# frontconnectors.net
KiCad netlist of a schematic drawn in Altium Designer
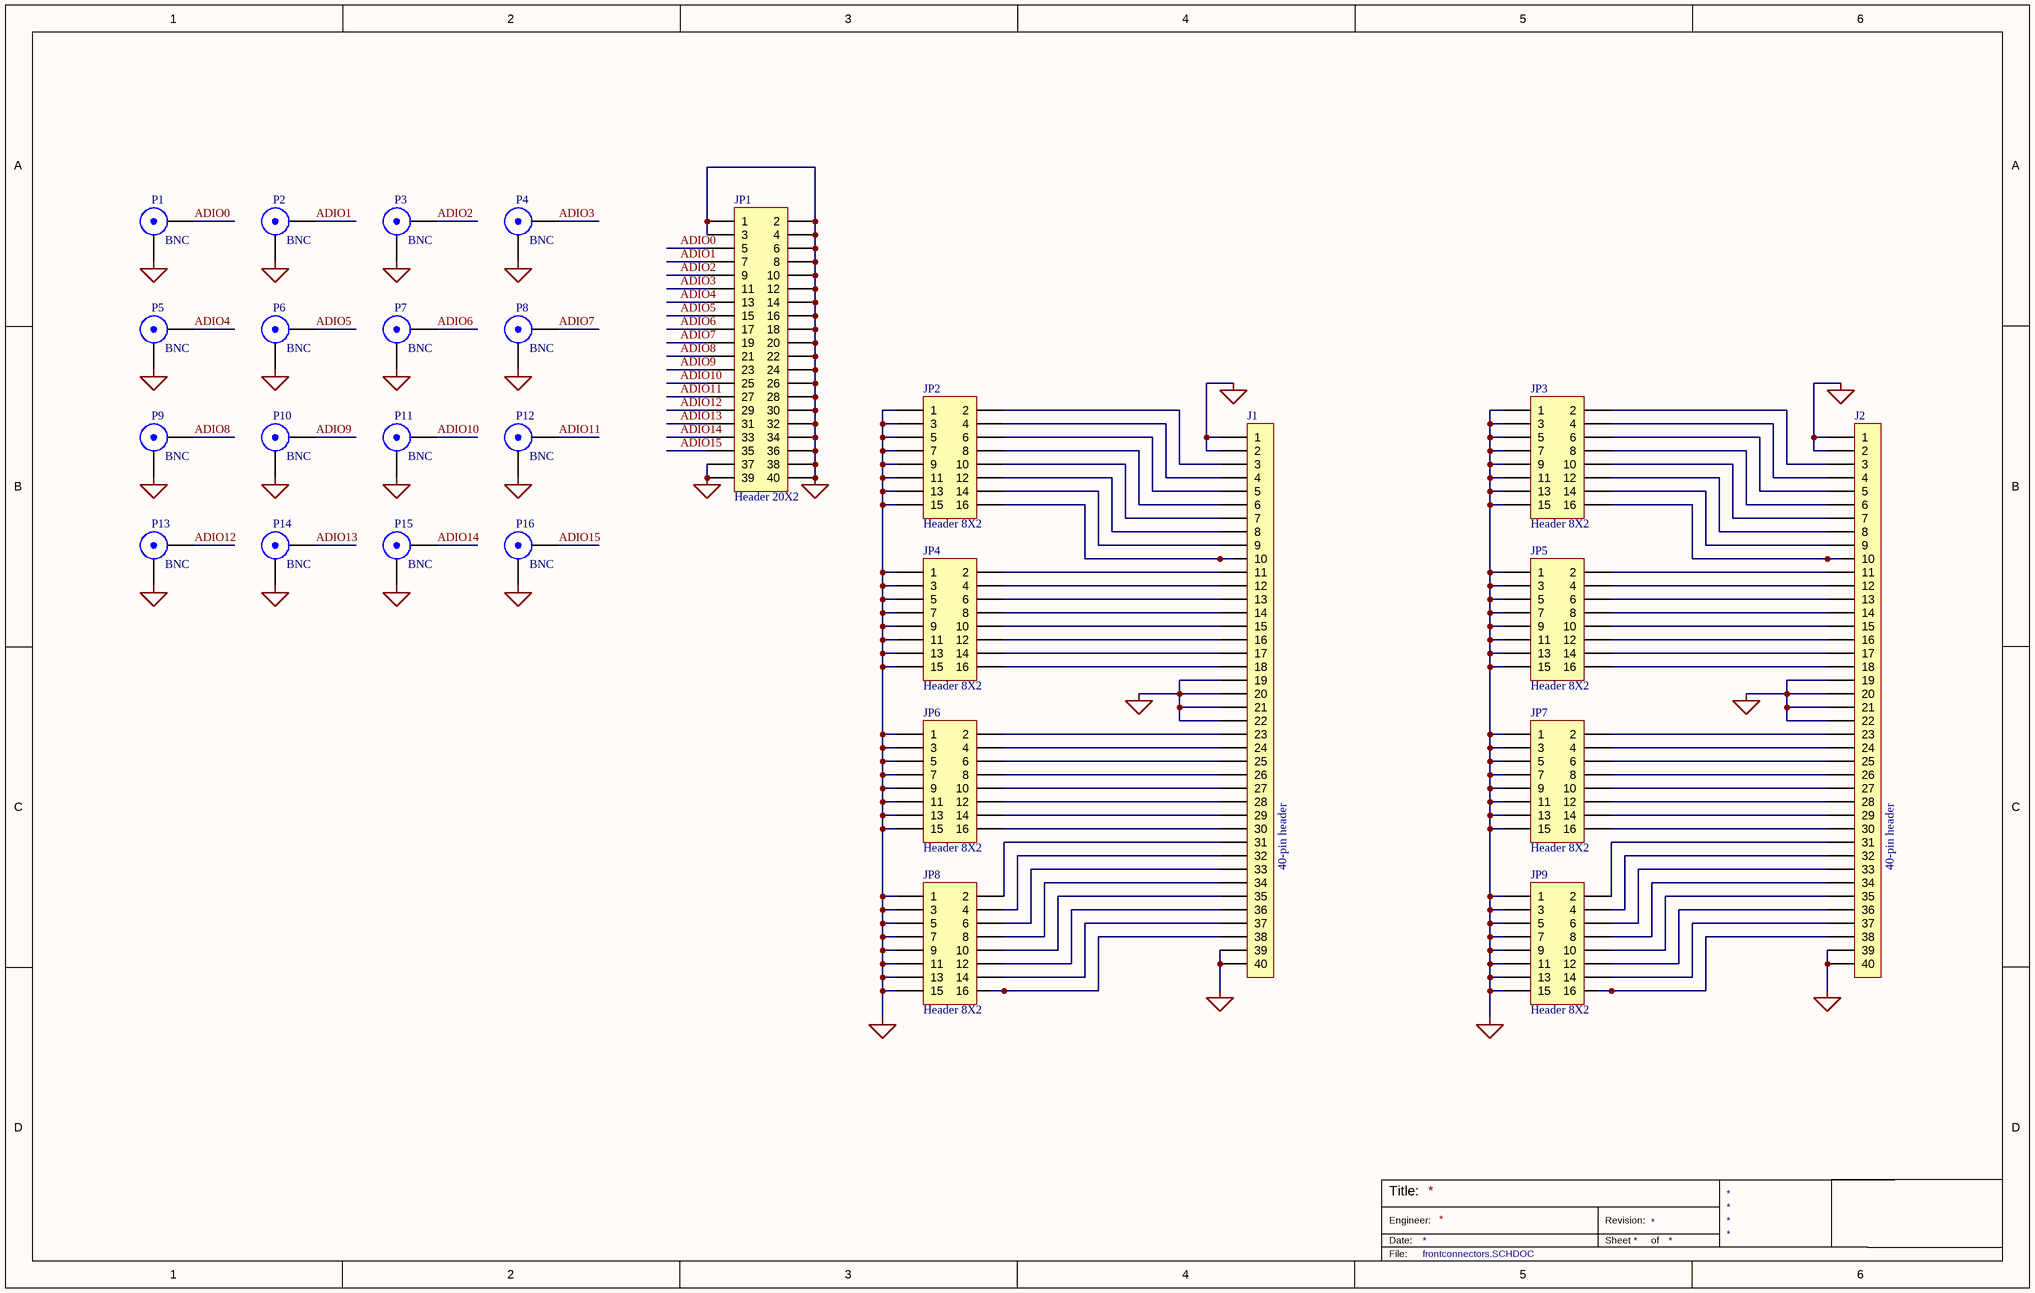
[diagram p0: frontconnectors.SCHDOC]

(export (version "E")
  (design (tool "Eeschema 10.0.6"))
  (components
    (comp (ref "J1")
      (value "40-pin header")
      (footprint "HDR2X20")
      (description "Simple 40pin connector")
      (libsource (lib "My devices") (part "40PINHEADER"))
    )
    (comp (ref "J2")
      (value "40-pin header")
      (footprint "HDR2X20")
      (description "Simple 40pin connector")
      (libsource (lib "My devices") (part "40PINHEADER"))
    )
    (comp (ref "JP1")
      (value "Header 20X2")
      (footprint "HDR2X20")
      (description "Header, 20-Pin, Dual row")
      (fields (field (name "MANUFACTURER") "Generic Components") (field (name "PUBLISHER") "Altium Limited"))
      (libsource (lib "Miscellaneous Connectors") (part "Header 20X2"))
    )
    (comp (ref "JP2")
      (value "Header 8X2")
      (footprint "HDR2X8")
      (description "Header, 8-Pin, Dual row")
      (fields (field (name "MANUFACTURER") "Generic Components") (field (name "PUBLISHER") "Altium Limited"))
      (libsource (lib "Miscellaneous Connectors") (part "Header 8X2"))
    )
    (comp (ref "JP3")
      (value "Header 8X2")
      (footprint "HDR2X8")
      (description "Header, 8-Pin, Dual row")
      (fields (field (name "MANUFACTURER") "Generic Components") (field (name "PUBLISHER") "Altium Limited"))
      (libsource (lib "Miscellaneous Connectors") (part "Header 8X2"))
    )
    (comp (ref "JP4")
      (value "Header 8X2")
      (footprint "HDR2X8")
      (description "Header, 8-Pin, Dual row")
      (fields (field (name "MANUFACTURER") "Generic Components") (field (name "PUBLISHER") "Altium Limited"))
      (libsource (lib "Miscellaneous Connectors") (part "Header 8X2"))
    )
    (comp (ref "JP5")
      (value "Header 8X2")
      (footprint "HDR2X8")
      (description "Header, 8-Pin, Dual row")
      (fields (field (name "MANUFACTURER") "Generic Components") (field (name "PUBLISHER") "Altium Limited"))
      (libsource (lib "Miscellaneous Connectors") (part "Header 8X2"))
    )
    (comp (ref "JP6")
      (value "Header 8X2")
      (footprint "HDR2X8")
      (description "Header, 8-Pin, Dual row")
      (fields (field (name "MANUFACTURER") "Generic Components") (field (name "PUBLISHER") "Altium Limited"))
      (libsource (lib "Miscellaneous Connectors") (part "Header 8X2"))
    )
    (comp (ref "JP7")
      (value "Header 8X2")
      (footprint "HDR2X8")
      (description "Header, 8-Pin, Dual row")
      (fields (field (name "MANUFACTURER") "Generic Components") (field (name "PUBLISHER") "Altium Limited"))
      (libsource (lib "Miscellaneous Connectors") (part "Header 8X2"))
    )
    (comp (ref "JP8")
      (value "Header 8X2")
      (footprint "HDR2X8")
      (description "Header, 8-Pin, Dual row")
      (fields (field (name "MANUFACTURER") "Generic Components") (field (name "PUBLISHER") "Altium Limited"))
      (libsource (lib "Miscellaneous Connectors") (part "Header 8X2"))
    )
    (comp (ref "JP9")
      (value "Header 8X2")
      (footprint "HDR2X8")
      (description "Header, 8-Pin, Dual row")
      (fields (field (name "MANUFACTURER") "Generic Components") (field (name "PUBLISHER") "Altium Limited"))
      (libsource (lib "Miscellaneous Connectors") (part "Header 8X2"))
    )
    (comp (ref "P1")
      (value "BNC")
      (footprint "Vertical BNC 227699-1")
      (description "BNC Elbow Connector")
      (fields (field (name "MANUFACTURER") "Generic Components") (field (name "PUBLISHER") "Altium Limited"))
      (libsource (lib "Miscellaneous Connectors") (part "BNC"))
    )
    (comp (ref "P2")
      (value "BNC")
      (footprint "Vertical BNC 227699-1")
      (description "BNC Elbow Connector")
      (fields (field (name "MANUFACTURER") "Generic Components") (field (name "PUBLISHER") "Altium Limited"))
      (libsource (lib "Miscellaneous Connectors") (part "BNC"))
    )
    (comp (ref "P3")
      (value "BNC")
      (footprint "Vertical BNC 227699-1")
      (description "BNC Elbow Connector")
      (fields (field (name "MANUFACTURER") "Generic Components") (field (name "PUBLISHER") "Altium Limited"))
      (libsource (lib "Miscellaneous Connectors") (part "BNC"))
    )
    (comp (ref "P4")
      (value "BNC")
      (footprint "Vertical BNC 227699-1")
      (description "BNC Elbow Connector")
      (fields (field (name "MANUFACTURER") "Generic Components") (field (name "PUBLISHER") "Altium Limited"))
      (libsource (lib "Miscellaneous Connectors") (part "BNC"))
    )
    (comp (ref "P5")
      (value "BNC")
      (footprint "Vertical BNC 227699-1")
      (description "BNC Elbow Connector")
      (fields (field (name "MANUFACTURER") "Generic Components") (field (name "PUBLISHER") "Altium Limited"))
      (libsource (lib "Miscellaneous Connectors") (part "BNC"))
    )
    (comp (ref "P6")
      (value "BNC")
      (footprint "Vertical BNC 227699-1")
      (description "BNC Elbow Connector")
      (fields (field (name "MANUFACTURER") "Generic Components") (field (name "PUBLISHER") "Altium Limited"))
      (libsource (lib "Miscellaneous Connectors") (part "BNC"))
    )
    (comp (ref "P7")
      (value "BNC")
      (footprint "Vertical BNC 227699-1")
      (description "BNC Elbow Connector")
      (fields (field (name "MANUFACTURER") "Generic Components") (field (name "PUBLISHER") "Altium Limited"))
      (libsource (lib "Miscellaneous Connectors") (part "BNC"))
    )
    (comp (ref "P8")
      (value "BNC")
      (footprint "Vertical BNC 227699-1")
      (description "BNC Elbow Connector")
      (fields (field (name "MANUFACTURER") "Generic Components") (field (name "PUBLISHER") "Altium Limited"))
      (libsource (lib "Miscellaneous Connectors") (part "BNC"))
    )
    (comp (ref "P9")
      (value "BNC")
      (footprint "Vertical BNC 227699-1")
      (description "BNC Elbow Connector")
      (fields (field (name "MANUFACTURER") "Generic Components") (field (name "PUBLISHER") "Altium Limited"))
      (libsource (lib "Miscellaneous Connectors") (part "BNC"))
    )
    (comp (ref "P10")
      (value "BNC")
      (footprint "Vertical BNC 227699-1")
      (description "BNC Elbow Connector")
      (fields (field (name "MANUFACTURER") "Generic Components") (field (name "PUBLISHER") "Altium Limited"))
      (libsource (lib "Miscellaneous Connectors") (part "BNC"))
    )
    (comp (ref "P11")
      (value "BNC")
      (footprint "Vertical BNC 227699-1")
      (description "BNC Elbow Connector")
      (fields (field (name "MANUFACTURER") "Generic Components") (field (name "PUBLISHER") "Altium Limited"))
      (libsource (lib "Miscellaneous Connectors") (part "BNC"))
    )
    (comp (ref "P12")
      (value "BNC")
      (footprint "Vertical BNC 227699-1")
      (description "BNC Elbow Connector")
      (fields (field (name "MANUFACTURER") "Generic Components") (field (name "PUBLISHER") "Altium Limited"))
      (libsource (lib "Miscellaneous Connectors") (part "BNC"))
    )
    (comp (ref "P13")
      (value "BNC")
      (footprint "Vertical BNC 227699-1")
      (description "BNC Elbow Connector")
      (fields (field (name "MANUFACTURER") "Generic Components") (field (name "PUBLISHER") "Altium Limited"))
      (libsource (lib "Miscellaneous Connectors") (part "BNC"))
    )
    (comp (ref "P14")
      (value "BNC")
      (footprint "Vertical BNC 227699-1")
      (description "BNC Elbow Connector")
      (fields (field (name "MANUFACTURER") "Generic Components") (field (name "PUBLISHER") "Altium Limited"))
      (libsource (lib "Miscellaneous Connectors") (part "BNC"))
    )
    (comp (ref "P15")
      (value "BNC")
      (footprint "Vertical BNC 227699-1")
      (description "BNC Elbow Connector")
      (fields (field (name "MANUFACTURER") "Generic Components") (field (name "PUBLISHER") "Altium Limited"))
      (libsource (lib "Miscellaneous Connectors") (part "BNC"))
    )
    (comp (ref "P16")
      (value "BNC")
      (footprint "Vertical BNC 227699-1")
      (description "BNC Elbow Connector")
      (fields (field (name "MANUFACTURER") "Generic Components") (field (name "PUBLISHER") "Altium Limited"))
      (libsource (lib "Miscellaneous Connectors") (part "BNC"))
    )
  )
  (nets
    (net (code "1") (name "/ADIO0") (class "Default")
      (node (ref "JP1") (pin "5") (pinfunction "5_5") (pintype "passive"))
      (node (ref "P1") (pin "1") (pinfunction "X_1") (pintype "passive"))
    )
    (net (code "2") (name "/ADIO1") (class "Default")
      (node (ref "JP1") (pin "7") (pinfunction "7_7") (pintype "passive"))
      (node (ref "P2") (pin "1") (pinfunction "X_1") (pintype "passive"))
    )
    (net (code "3") (name "/ADIO2") (class "Default")
      (node (ref "JP1") (pin "9") (pinfunction "9_9") (pintype "passive"))
      (node (ref "P3") (pin "1") (pinfunction "X_1") (pintype "passive"))
    )
    (net (code "4") (name "/ADIO3") (class "Default")
      (node (ref "JP1") (pin "11") (pinfunction "11_11") (pintype "passive"))
      (node (ref "P4") (pin "1") (pinfunction "X_1") (pintype "passive"))
    )
    (net (code "5") (name "/ADIO4") (class "Default")
      (node (ref "JP1") (pin "13") (pinfunction "13_13") (pintype "passive"))
      (node (ref "P5") (pin "1") (pinfunction "X_1") (pintype "passive"))
    )
    (net (code "6") (name "/ADIO5") (class "Default")
      (node (ref "JP1") (pin "15") (pinfunction "15_15") (pintype "passive"))
      (node (ref "P6") (pin "1") (pinfunction "X_1") (pintype "passive"))
    )
    (net (code "7") (name "/ADIO6") (class "Default")
      (node (ref "JP1") (pin "17") (pinfunction "17_17") (pintype "passive"))
      (node (ref "P7") (pin "1") (pinfunction "X_1") (pintype "passive"))
    )
    (net (code "8") (name "/ADIO7") (class "Default")
      (node (ref "JP1") (pin "19") (pinfunction "19_19") (pintype "passive"))
      (node (ref "P8") (pin "1") (pinfunction "X_1") (pintype "passive"))
    )
    (net (code "9") (name "/ADIO8") (class "Default")
      (node (ref "JP1") (pin "21") (pinfunction "21_21") (pintype "passive"))
      (node (ref "P9") (pin "1") (pinfunction "X_1") (pintype "passive"))
    )
    (net (code "10") (name "/ADIO9") (class "Default")
      (node (ref "JP1") (pin "23") (pinfunction "23_23") (pintype "passive"))
      (node (ref "P10") (pin "1") (pinfunction "X_1") (pintype "passive"))
    )
    (net (code "11") (name "/ADIO10") (class "Default")
      (node (ref "JP1") (pin "25") (pinfunction "25_25") (pintype "passive"))
      (node (ref "P11") (pin "1") (pinfunction "X_1") (pintype "passive"))
    )
    (net (code "12") (name "/ADIO11") (class "Default")
      (node (ref "JP1") (pin "27") (pinfunction "27_27") (pintype "passive"))
      (node (ref "P12") (pin "1") (pinfunction "X_1") (pintype "passive"))
    )
    (net (code "13") (name "/ADIO12") (class "Default")
      (node (ref "JP1") (pin "29") (pinfunction "29_29") (pintype "passive"))
      (node (ref "P13") (pin "1") (pinfunction "X_1") (pintype "passive"))
    )
    (net (code "14") (name "/ADIO13") (class "Default")
      (node (ref "JP1") (pin "31") (pinfunction "31_31") (pintype "passive"))
      (node (ref "P14") (pin "1") (pinfunction "X_1") (pintype "passive"))
    )
    (net (code "15") (name "/ADIO14") (class "Default")
      (node (ref "JP1") (pin "33") (pinfunction "33_33") (pintype "passive"))
      (node (ref "P15") (pin "1") (pinfunction "X_1") (pintype "passive"))
    )
    (net (code "16") (name "/ADIO15") (class "Default")
      (node (ref "JP1") (pin "35") (pinfunction "35_35") (pintype "passive"))
      (node (ref "P16") (pin "1") (pinfunction "X_1") (pintype "passive"))
    )
    (net (code "17") (name "AGND") (class "Default")
      (node (ref "JP1") (pin "1") (pinfunction "1_1") (pintype "passive"))
      (node (ref "JP1") (pin "10") (pinfunction "10_10") (pintype "passive"))
      (node (ref "JP1") (pin "12") (pinfunction "12_12") (pintype "passive"))
      (node (ref "JP1") (pin "14") (pinfunction "14_14") (pintype "passive"))
      (node (ref "JP1") (pin "16") (pinfunction "16_16") (pintype "passive"))
      (node (ref "JP1") (pin "18") (pinfunction "18_18") (pintype "passive"))
      (node (ref "JP1") (pin "2") (pinfunction "2_2") (pintype "passive"))
      (node (ref "JP1") (pin "20") (pinfunction "20_20") (pintype "passive"))
      (node (ref "JP1") (pin "22") (pinfunction "22_22") (pintype "passive"))
      (node (ref "JP1") (pin "24") (pinfunction "24_24") (pintype "passive"))
      (node (ref "JP1") (pin "26") (pinfunction "26_26") (pintype "passive"))
      (node (ref "JP1") (pin "28") (pinfunction "28_28") (pintype "passive"))
      (node (ref "JP1") (pin "3") (pinfunction "3_3") (pintype "passive"))
      (node (ref "JP1") (pin "30") (pinfunction "30_30") (pintype "passive"))
      (node (ref "JP1") (pin "32") (pinfunction "32_32") (pintype "passive"))
      (node (ref "JP1") (pin "34") (pinfunction "34_34") (pintype "passive"))
      (node (ref "JP1") (pin "36") (pinfunction "36_36") (pintype "passive"))
      (node (ref "JP1") (pin "37") (pinfunction "37_37") (pintype "passive"))
      (node (ref "JP1") (pin "38") (pinfunction "38_38") (pintype "passive"))
      (node (ref "JP1") (pin "39") (pinfunction "39_39") (pintype "passive"))
      (node (ref "JP1") (pin "4") (pinfunction "4_4") (pintype "passive"))
      (node (ref "JP1") (pin "40") (pinfunction "40_40") (pintype "passive"))
      (node (ref "JP1") (pin "6") (pinfunction "6_6") (pintype "passive"))
      (node (ref "JP1") (pin "8") (pinfunction "8_8") (pintype "passive"))
      (node (ref "P1") (pin "2") (pinfunction "Y_2") (pintype "passive"))
      (node (ref "P10") (pin "2") (pinfunction "Y_2") (pintype "passive"))
      (node (ref "P11") (pin "2") (pinfunction "Y_2") (pintype "passive"))
      (node (ref "P12") (pin "2") (pinfunction "Y_2") (pintype "passive"))
      (node (ref "P13") (pin "2") (pinfunction "Y_2") (pintype "passive"))
      (node (ref "P14") (pin "2") (pinfunction "Y_2") (pintype "passive"))
      (node (ref "P15") (pin "2") (pinfunction "Y_2") (pintype "passive"))
      (node (ref "P16") (pin "2") (pinfunction "Y_2") (pintype "passive"))
      (node (ref "P2") (pin "2") (pinfunction "Y_2") (pintype "passive"))
      (node (ref "P3") (pin "2") (pinfunction "Y_2") (pintype "passive"))
      (node (ref "P4") (pin "2") (pinfunction "Y_2") (pintype "passive"))
      (node (ref "P5") (pin "2") (pinfunction "Y_2") (pintype "passive"))
      (node (ref "P6") (pin "2") (pinfunction "Y_2") (pintype "passive"))
      (node (ref "P7") (pin "2") (pinfunction "Y_2") (pintype "passive"))
      (node (ref "P8") (pin "2") (pinfunction "Y_2") (pintype "passive"))
      (node (ref "P9") (pin "2") (pinfunction "Y_2") (pintype "passive"))
    )
    (net (code "18") (name "DGND") (class "Default")
      (node (ref "J1") (pin "1") (pinfunction "1_1") (pintype "passive"))
      (node (ref "J1") (pin "19") (pinfunction "19_19") (pintype "passive"))
      (node (ref "J1") (pin "2") (pinfunction "2_2") (pintype "passive"))
      (node (ref "J1") (pin "20") (pinfunction "20_20") (pintype "passive"))
      (node (ref "J1") (pin "21") (pinfunction "21_21") (pintype "passive"))
      (node (ref "J1") (pin "22") (pinfunction "22_22") (pintype "passive"))
      (node (ref "J1") (pin "39") (pinfunction "39_39") (pintype "passive"))
      (node (ref "J1") (pin "40") (pinfunction "40_40") (pintype "passive"))
      (node (ref "J2") (pin "1") (pinfunction "1_1") (pintype "passive"))
      (node (ref "J2") (pin "19") (pinfunction "19_19") (pintype "passive"))
      (node (ref "J2") (pin "2") (pinfunction "2_2") (pintype "passive"))
      (node (ref "J2") (pin "20") (pinfunction "20_20") (pintype "passive"))
      (node (ref "J2") (pin "21") (pinfunction "21_21") (pintype "passive"))
      (node (ref "J2") (pin "22") (pinfunction "22_22") (pintype "passive"))
      (node (ref "J2") (pin "39") (pinfunction "39_39") (pintype "passive"))
      (node (ref "J2") (pin "40") (pinfunction "40_40") (pintype "passive"))
      (node (ref "JP2") (pin "1") (pinfunction "1_1") (pintype "passive"))
      (node (ref "JP2") (pin "11") (pinfunction "11_11") (pintype "passive"))
      (node (ref "JP2") (pin "13") (pinfunction "13_13") (pintype "passive"))
      (node (ref "JP2") (pin "15") (pinfunction "15_15") (pintype "passive"))
      (node (ref "JP2") (pin "3") (pinfunction "3_3") (pintype "passive"))
      (node (ref "JP2") (pin "5") (pinfunction "5_5") (pintype "passive"))
      (node (ref "JP2") (pin "7") (pinfunction "7_7") (pintype "passive"))
      (node (ref "JP2") (pin "9") (pinfunction "9_9") (pintype "passive"))
      (node (ref "JP3") (pin "1") (pinfunction "1_1") (pintype "passive"))
      (node (ref "JP3") (pin "11") (pinfunction "11_11") (pintype "passive"))
      (node (ref "JP3") (pin "13") (pinfunction "13_13") (pintype "passive"))
      (node (ref "JP3") (pin "15") (pinfunction "15_15") (pintype "passive"))
      (node (ref "JP3") (pin "3") (pinfunction "3_3") (pintype "passive"))
      (node (ref "JP3") (pin "5") (pinfunction "5_5") (pintype "passive"))
      (node (ref "JP3") (pin "7") (pinfunction "7_7") (pintype "passive"))
      (node (ref "JP3") (pin "9") (pinfunction "9_9") (pintype "passive"))
      (node (ref "JP4") (pin "1") (pinfunction "1_1") (pintype "passive"))
      (node (ref "JP4") (pin "11") (pinfunction "11_11") (pintype "passive"))
      (node (ref "JP4") (pin "13") (pinfunction "13_13") (pintype "passive"))
      (node (ref "JP4") (pin "15") (pinfunction "15_15") (pintype "passive"))
      (node (ref "JP4") (pin "3") (pinfunction "3_3") (pintype "passive"))
      (node (ref "JP4") (pin "5") (pinfunction "5_5") (pintype "passive"))
      (node (ref "JP4") (pin "7") (pinfunction "7_7") (pintype "passive"))
      (node (ref "JP4") (pin "9") (pinfunction "9_9") (pintype "passive"))
      (node (ref "JP5") (pin "1") (pinfunction "1_1") (pintype "passive"))
      (node (ref "JP5") (pin "11") (pinfunction "11_11") (pintype "passive"))
      (node (ref "JP5") (pin "13") (pinfunction "13_13") (pintype "passive"))
      (node (ref "JP5") (pin "15") (pinfunction "15_15") (pintype "passive"))
      (node (ref "JP5") (pin "3") (pinfunction "3_3") (pintype "passive"))
      (node (ref "JP5") (pin "5") (pinfunction "5_5") (pintype "passive"))
      (node (ref "JP5") (pin "7") (pinfunction "7_7") (pintype "passive"))
      (node (ref "JP5") (pin "9") (pinfunction "9_9") (pintype "passive"))
      (node (ref "JP6") (pin "1") (pinfunction "1_1") (pintype "passive"))
      (node (ref "JP6") (pin "11") (pinfunction "11_11") (pintype "passive"))
      (node (ref "JP6") (pin "13") (pinfunction "13_13") (pintype "passive"))
      (node (ref "JP6") (pin "15") (pinfunction "15_15") (pintype "passive"))
      (node (ref "JP6") (pin "3") (pinfunction "3_3") (pintype "passive"))
      (node (ref "JP6") (pin "5") (pinfunction "5_5") (pintype "passive"))
      (node (ref "JP6") (pin "7") (pinfunction "7_7") (pintype "passive"))
      (node (ref "JP6") (pin "9") (pinfunction "9_9") (pintype "passive"))
      (node (ref "JP7") (pin "1") (pinfunction "1_1") (pintype "passive"))
      (node (ref "JP7") (pin "11") (pinfunction "11_11") (pintype "passive"))
      (node (ref "JP7") (pin "13") (pinfunction "13_13") (pintype "passive"))
      (node (ref "JP7") (pin "15") (pinfunction "15_15") (pintype "passive"))
      (node (ref "JP7") (pin "3") (pinfunction "3_3") (pintype "passive"))
      (node (ref "JP7") (pin "5") (pinfunction "5_5") (pintype "passive"))
      (node (ref "JP7") (pin "7") (pinfunction "7_7") (pintype "passive"))
      (node (ref "JP7") (pin "9") (pinfunction "9_9") (pintype "passive"))
      (node (ref "JP8") (pin "1") (pinfunction "1_1") (pintype "passive"))
      (node (ref "JP8") (pin "11") (pinfunction "11_11") (pintype "passive"))
      (node (ref "JP8") (pin "13") (pinfunction "13_13") (pintype "passive"))
      (node (ref "JP8") (pin "15") (pinfunction "15_15") (pintype "passive"))
      (node (ref "JP8") (pin "3") (pinfunction "3_3") (pintype "passive"))
      (node (ref "JP8") (pin "5") (pinfunction "5_5") (pintype "passive"))
      (node (ref "JP8") (pin "7") (pinfunction "7_7") (pintype "passive"))
      (node (ref "JP8") (pin "9") (pinfunction "9_9") (pintype "passive"))
      (node (ref "JP9") (pin "1") (pinfunction "1_1") (pintype "passive"))
      (node (ref "JP9") (pin "11") (pinfunction "11_11") (pintype "passive"))
      (node (ref "JP9") (pin "13") (pinfunction "13_13") (pintype "passive"))
      (node (ref "JP9") (pin "15") (pinfunction "15_15") (pintype "passive"))
      (node (ref "JP9") (pin "3") (pinfunction "3_3") (pintype "passive"))
      (node (ref "JP9") (pin "5") (pinfunction "5_5") (pintype "passive"))
      (node (ref "JP9") (pin "7") (pinfunction "7_7") (pintype "passive"))
      (node (ref "JP9") (pin "9") (pinfunction "9_9") (pintype "passive"))
    )
    (net (code "19") (name "Net-(J1-Pad3)") (class "Default")
      (node (ref "J1") (pin "3") (pinfunction "3_3") (pintype "passive"))
      (node (ref "JP2") (pin "2") (pinfunction "2_2") (pintype "passive"))
    )
    (net (code "20") (name "Net-(J1-Pad4)") (class "Default")
      (node (ref "J1") (pin "4") (pinfunction "4_4") (pintype "passive"))
      (node (ref "JP2") (pin "4") (pinfunction "4_4") (pintype "passive"))
    )
    (net (code "21") (name "Net-(J1-Pad5)") (class "Default")
      (node (ref "J1") (pin "5") (pinfunction "5_5") (pintype "passive"))
      (node (ref "JP2") (pin "6") (pinfunction "6_6") (pintype "passive"))
    )
    (net (code "22") (name "Net-(J1-Pad6)") (class "Default")
      (node (ref "J1") (pin "6") (pinfunction "6_6") (pintype "passive"))
      (node (ref "JP2") (pin "8") (pinfunction "8_8") (pintype "passive"))
    )
    (net (code "23") (name "Net-(J1-Pad7)") (class "Default")
      (node (ref "J1") (pin "7") (pinfunction "7_7") (pintype "passive"))
      (node (ref "JP2") (pin "10") (pinfunction "10_10") (pintype "passive"))
    )
    (net (code "24") (name "Net-(J1-Pad8)") (class "Default")
      (node (ref "J1") (pin "8") (pinfunction "8_8") (pintype "passive"))
      (node (ref "JP2") (pin "12") (pinfunction "12_12") (pintype "passive"))
    )
    (net (code "25") (name "Net-(J1-Pad9)") (class "Default")
      (node (ref "J1") (pin "9") (pinfunction "9_9") (pintype "passive"))
      (node (ref "JP2") (pin "14") (pinfunction "14_14") (pintype "passive"))
    )
    (net (code "26") (name "Net-(J1-Pad10)") (class "Default")
      (node (ref "J1") (pin "10") (pinfunction "10_10") (pintype "passive"))
      (node (ref "JP2") (pin "16") (pinfunction "16_16") (pintype "passive"))
    )
    (net (code "27") (name "Net-(J1-Pad11)") (class "Default")
      (node (ref "J1") (pin "11") (pinfunction "11_11") (pintype "passive"))
      (node (ref "JP4") (pin "2") (pinfunction "2_2") (pintype "passive"))
    )
    (net (code "28") (name "Net-(J1-Pad12)") (class "Default")
      (node (ref "J1") (pin "12") (pinfunction "12_12") (pintype "passive"))
      (node (ref "JP4") (pin "4") (pinfunction "4_4") (pintype "passive"))
    )
    (net (code "29") (name "Net-(J1-Pad13)") (class "Default")
      (node (ref "J1") (pin "13") (pinfunction "13_13") (pintype "passive"))
      (node (ref "JP4") (pin "6") (pinfunction "6_6") (pintype "passive"))
    )
    (net (code "30") (name "Net-(J1-Pad14)") (class "Default")
      (node (ref "J1") (pin "14") (pinfunction "14_14") (pintype "passive"))
      (node (ref "JP4") (pin "8") (pinfunction "8_8") (pintype "passive"))
    )
    (net (code "31") (name "Net-(J1-Pad15)") (class "Default")
      (node (ref "J1") (pin "15") (pinfunction "15_15") (pintype "passive"))
      (node (ref "JP4") (pin "10") (pinfunction "10_10") (pintype "passive"))
    )
    (net (code "32") (name "Net-(J1-Pad16)") (class "Default")
      (node (ref "J1") (pin "16") (pinfunction "16_16") (pintype "passive"))
      (node (ref "JP4") (pin "12") (pinfunction "12_12") (pintype "passive"))
    )
    (net (code "33") (name "Net-(J1-Pad17)") (class "Default")
      (node (ref "J1") (pin "17") (pinfunction "17_17") (pintype "passive"))
      (node (ref "JP4") (pin "14") (pinfunction "14_14") (pintype "passive"))
    )
    (net (code "34") (name "Net-(J1-Pad18)") (class "Default")
      (node (ref "J1") (pin "18") (pinfunction "18_18") (pintype "passive"))
      (node (ref "JP4") (pin "16") (pinfunction "16_16") (pintype "passive"))
    )
    (net (code "35") (name "Net-(J1-Pad23)") (class "Default")
      (node (ref "J1") (pin "23") (pinfunction "23_23") (pintype "passive"))
      (node (ref "JP6") (pin "2") (pinfunction "2_2") (pintype "passive"))
    )
    (net (code "36") (name "Net-(J1-Pad24)") (class "Default")
      (node (ref "J1") (pin "24") (pinfunction "24_24") (pintype "passive"))
      (node (ref "JP6") (pin "4") (pinfunction "4_4") (pintype "passive"))
    )
    (net (code "37") (name "Net-(J1-Pad25)") (class "Default")
      (node (ref "J1") (pin "25") (pinfunction "25_25") (pintype "passive"))
      (node (ref "JP6") (pin "6") (pinfunction "6_6") (pintype "passive"))
    )
    (net (code "38") (name "Net-(J1-Pad26)") (class "Default")
      (node (ref "J1") (pin "26") (pinfunction "26_26") (pintype "passive"))
      (node (ref "JP6") (pin "8") (pinfunction "8_8") (pintype "passive"))
    )
    (net (code "39") (name "Net-(J1-Pad27)") (class "Default")
      (node (ref "J1") (pin "27") (pinfunction "27_27") (pintype "passive"))
      (node (ref "JP6") (pin "10") (pinfunction "10_10") (pintype "passive"))
    )
    (net (code "40") (name "Net-(J1-Pad28)") (class "Default")
      (node (ref "J1") (pin "28") (pinfunction "28_28") (pintype "passive"))
      (node (ref "JP6") (pin "12") (pinfunction "12_12") (pintype "passive"))
    )
    (net (code "41") (name "Net-(J1-Pad29)") (class "Default")
      (node (ref "J1") (pin "29") (pinfunction "29_29") (pintype "passive"))
      (node (ref "JP6") (pin "14") (pinfunction "14_14") (pintype "passive"))
    )
    (net (code "42") (name "Net-(J1-Pad30)") (class "Default")
      (node (ref "J1") (pin "30") (pinfunction "30_30") (pintype "passive"))
      (node (ref "JP6") (pin "16") (pinfunction "16_16") (pintype "passive"))
    )
    (net (code "43") (name "Net-(J1-Pad31)") (class "Default")
      (node (ref "J1") (pin "31") (pinfunction "31_31") (pintype "passive"))
      (node (ref "JP8") (pin "2") (pinfunction "2_2") (pintype "passive"))
    )
    (net (code "44") (name "Net-(J1-Pad32)") (class "Default")
      (node (ref "J1") (pin "32") (pinfunction "32_32") (pintype "passive"))
      (node (ref "JP8") (pin "4") (pinfunction "4_4") (pintype "passive"))
    )
    (net (code "45") (name "Net-(J1-Pad33)") (class "Default")
      (node (ref "J1") (pin "33") (pinfunction "33_33") (pintype "passive"))
      (node (ref "JP8") (pin "6") (pinfunction "6_6") (pintype "passive"))
    )
    (net (code "46") (name "Net-(J1-Pad34)") (class "Default")
      (node (ref "J1") (pin "34") (pinfunction "34_34") (pintype "passive"))
      (node (ref "JP8") (pin "8") (pinfunction "8_8") (pintype "passive"))
    )
    (net (code "47") (name "Net-(J1-Pad35)") (class "Default")
      (node (ref "J1") (pin "35") (pinfunction "35_35") (pintype "passive"))
      (node (ref "JP8") (pin "10") (pinfunction "10_10") (pintype "passive"))
    )
    (net (code "48") (name "Net-(J1-Pad36)") (class "Default")
      (node (ref "J1") (pin "36") (pinfunction "36_36") (pintype "passive"))
      (node (ref "JP8") (pin "12") (pinfunction "12_12") (pintype "passive"))
    )
    (net (code "49") (name "Net-(J1-Pad37)") (class "Default")
      (node (ref "J1") (pin "37") (pinfunction "37_37") (pintype "passive"))
      (node (ref "JP8") (pin "14") (pinfunction "14_14") (pintype "passive"))
    )
    (net (code "50") (name "Net-(J1-Pad38)") (class "Default")
      (node (ref "J1") (pin "38") (pinfunction "38_38") (pintype "passive"))
      (node (ref "JP8") (pin "16") (pinfunction "16_16") (pintype "passive"))
    )
    (net (code "51") (name "Net-(J2-Pad3)") (class "Default")
      (node (ref "J2") (pin "3") (pinfunction "3_3") (pintype "passive"))
      (node (ref "JP3") (pin "2") (pinfunction "2_2") (pintype "passive"))
    )
    (net (code "52") (name "Net-(J2-Pad4)") (class "Default")
      (node (ref "J2") (pin "4") (pinfunction "4_4") (pintype "passive"))
      (node (ref "JP3") (pin "4") (pinfunction "4_4") (pintype "passive"))
    )
    (net (code "53") (name "Net-(J2-Pad5)") (class "Default")
      (node (ref "J2") (pin "5") (pinfunction "5_5") (pintype "passive"))
      (node (ref "JP3") (pin "6") (pinfunction "6_6") (pintype "passive"))
    )
    (net (code "54") (name "Net-(J2-Pad6)") (class "Default")
      (node (ref "J2") (pin "6") (pinfunction "6_6") (pintype "passive"))
      (node (ref "JP3") (pin "8") (pinfunction "8_8") (pintype "passive"))
    )
    (net (code "55") (name "Net-(J2-Pad7)") (class "Default")
      (node (ref "J2") (pin "7") (pinfunction "7_7") (pintype "passive"))
      (node (ref "JP3") (pin "10") (pinfunction "10_10") (pintype "passive"))
    )
    (net (code "56") (name "Net-(J2-Pad8)") (class "Default")
      (node (ref "J2") (pin "8") (pinfunction "8_8") (pintype "passive"))
      (node (ref "JP3") (pin "12") (pinfunction "12_12") (pintype "passive"))
    )
    (net (code "57") (name "Net-(J2-Pad9)") (class "Default")
      (node (ref "J2") (pin "9") (pinfunction "9_9") (pintype "passive"))
      (node (ref "JP3") (pin "14") (pinfunction "14_14") (pintype "passive"))
    )
    (net (code "58") (name "Net-(J2-Pad10)") (class "Default")
      (node (ref "J2") (pin "10") (pinfunction "10_10") (pintype "passive"))
      (node (ref "JP3") (pin "16") (pinfunction "16_16") (pintype "passive"))
    )
    (net (code "59") (name "Net-(J2-Pad11)") (class "Default")
      (node (ref "J2") (pin "11") (pinfunction "11_11") (pintype "passive"))
      (node (ref "JP5") (pin "2") (pinfunction "2_2") (pintype "passive"))
    )
    (net (code "60") (name "Net-(J2-Pad12)") (class "Default")
      (node (ref "J2") (pin "12") (pinfunction "12_12") (pintype "passive"))
      (node (ref "JP5") (pin "4") (pinfunction "4_4") (pintype "passive"))
    )
    (net (code "61") (name "Net-(J2-Pad13)") (class "Default")
      (node (ref "J2") (pin "13") (pinfunction "13_13") (pintype "passive"))
      (node (ref "JP5") (pin "6") (pinfunction "6_6") (pintype "passive"))
    )
    (net (code "62") (name "Net-(J2-Pad14)") (class "Default")
      (node (ref "J2") (pin "14") (pinfunction "14_14") (pintype "passive"))
      (node (ref "JP5") (pin "8") (pinfunction "8_8") (pintype "passive"))
    )
    (net (code "63") (name "Net-(J2-Pad15)") (class "Default")
      (node (ref "J2") (pin "15") (pinfunction "15_15") (pintype "passive"))
      (node (ref "JP5") (pin "10") (pinfunction "10_10") (pintype "passive"))
    )
    (net (code "64") (name "Net-(J2-Pad16)") (class "Default")
      (node (ref "J2") (pin "16") (pinfunction "16_16") (pintype "passive"))
      (node (ref "JP5") (pin "12") (pinfunction "12_12") (pintype "passive"))
    )
    (net (code "65") (name "Net-(J2-Pad17)") (class "Default")
      (node (ref "J2") (pin "17") (pinfunction "17_17") (pintype "passive"))
      (node (ref "JP5") (pin "14") (pinfunction "14_14") (pintype "passive"))
    )
    (net (code "66") (name "Net-(J2-Pad18)") (class "Default")
      (node (ref "J2") (pin "18") (pinfunction "18_18") (pintype "passive"))
      (node (ref "JP5") (pin "16") (pinfunction "16_16") (pintype "passive"))
    )
    (net (code "67") (name "Net-(J2-Pad23)") (class "Default")
      (node (ref "J2") (pin "23") (pinfunction "23_23") (pintype "passive"))
      (node (ref "JP7") (pin "2") (pinfunction "2_2") (pintype "passive"))
    )
    (net (code "68") (name "Net-(J2-Pad24)") (class "Default")
      (node (ref "J2") (pin "24") (pinfunction "24_24") (pintype "passive"))
      (node (ref "JP7") (pin "4") (pinfunction "4_4") (pintype "passive"))
    )
    (net (code "69") (name "Net-(J2-Pad25)") (class "Default")
      (node (ref "J2") (pin "25") (pinfunction "25_25") (pintype "passive"))
      (node (ref "JP7") (pin "6") (pinfunction "6_6") (pintype "passive"))
    )
    (net (code "70") (name "Net-(J2-Pad26)") (class "Default")
      (node (ref "J2") (pin "26") (pinfunction "26_26") (pintype "passive"))
      (node (ref "JP7") (pin "8") (pinfunction "8_8") (pintype "passive"))
    )
    (net (code "71") (name "Net-(J2-Pad27)") (class "Default")
      (node (ref "J2") (pin "27") (pinfunction "27_27") (pintype "passive"))
      (node (ref "JP7") (pin "10") (pinfunction "10_10") (pintype "passive"))
    )
    (net (code "72") (name "Net-(J2-Pad28)") (class "Default")
      (node (ref "J2") (pin "28") (pinfunction "28_28") (pintype "passive"))
      (node (ref "JP7") (pin "12") (pinfunction "12_12") (pintype "passive"))
    )
    (net (code "73") (name "Net-(J2-Pad29)") (class "Default")
      (node (ref "J2") (pin "29") (pinfunction "29_29") (pintype "passive"))
      (node (ref "JP7") (pin "14") (pinfunction "14_14") (pintype "passive"))
    )
    (net (code "74") (name "Net-(J2-Pad30)") (class "Default")
      (node (ref "J2") (pin "30") (pinfunction "30_30") (pintype "passive"))
      (node (ref "JP7") (pin "16") (pinfunction "16_16") (pintype "passive"))
    )
    (net (code "75") (name "Net-(J2-Pad31)") (class "Default")
      (node (ref "J2") (pin "31") (pinfunction "31_31") (pintype "passive"))
      (node (ref "JP9") (pin "2") (pinfunction "2_2") (pintype "passive"))
    )
    (net (code "76") (name "Net-(J2-Pad32)") (class "Default")
      (node (ref "J2") (pin "32") (pinfunction "32_32") (pintype "passive"))
      (node (ref "JP9") (pin "4") (pinfunction "4_4") (pintype "passive"))
    )
    (net (code "77") (name "Net-(J2-Pad33)") (class "Default")
      (node (ref "J2") (pin "33") (pinfunction "33_33") (pintype "passive"))
      (node (ref "JP9") (pin "6") (pinfunction "6_6") (pintype "passive"))
    )
    (net (code "78") (name "Net-(J2-Pad34)") (class "Default")
      (node (ref "J2") (pin "34") (pinfunction "34_34") (pintype "passive"))
      (node (ref "JP9") (pin "8") (pinfunction "8_8") (pintype "passive"))
    )
    (net (code "79") (name "Net-(J2-Pad35)") (class "Default")
      (node (ref "J2") (pin "35") (pinfunction "35_35") (pintype "passive"))
      (node (ref "JP9") (pin "10") (pinfunction "10_10") (pintype "passive"))
    )
    (net (code "80") (name "Net-(J2-Pad36)") (class "Default")
      (node (ref "J2") (pin "36") (pinfunction "36_36") (pintype "passive"))
      (node (ref "JP9") (pin "12") (pinfunction "12_12") (pintype "passive"))
    )
    (net (code "81") (name "Net-(J2-Pad37)") (class "Default")
      (node (ref "J2") (pin "37") (pinfunction "37_37") (pintype "passive"))
      (node (ref "JP9") (pin "14") (pinfunction "14_14") (pintype "passive"))
    )
    (net (code "82") (name "Net-(J2-Pad38)") (class "Default")
      (node (ref "J2") (pin "38") (pinfunction "38_38") (pintype "passive"))
      (node (ref "JP9") (pin "16") (pinfunction "16_16") (pintype "passive"))
    )
  )
)
